# BOTTOM_BRD_v_1_0_2.net
KiCad netlist of a schematic drawn in EAGLE
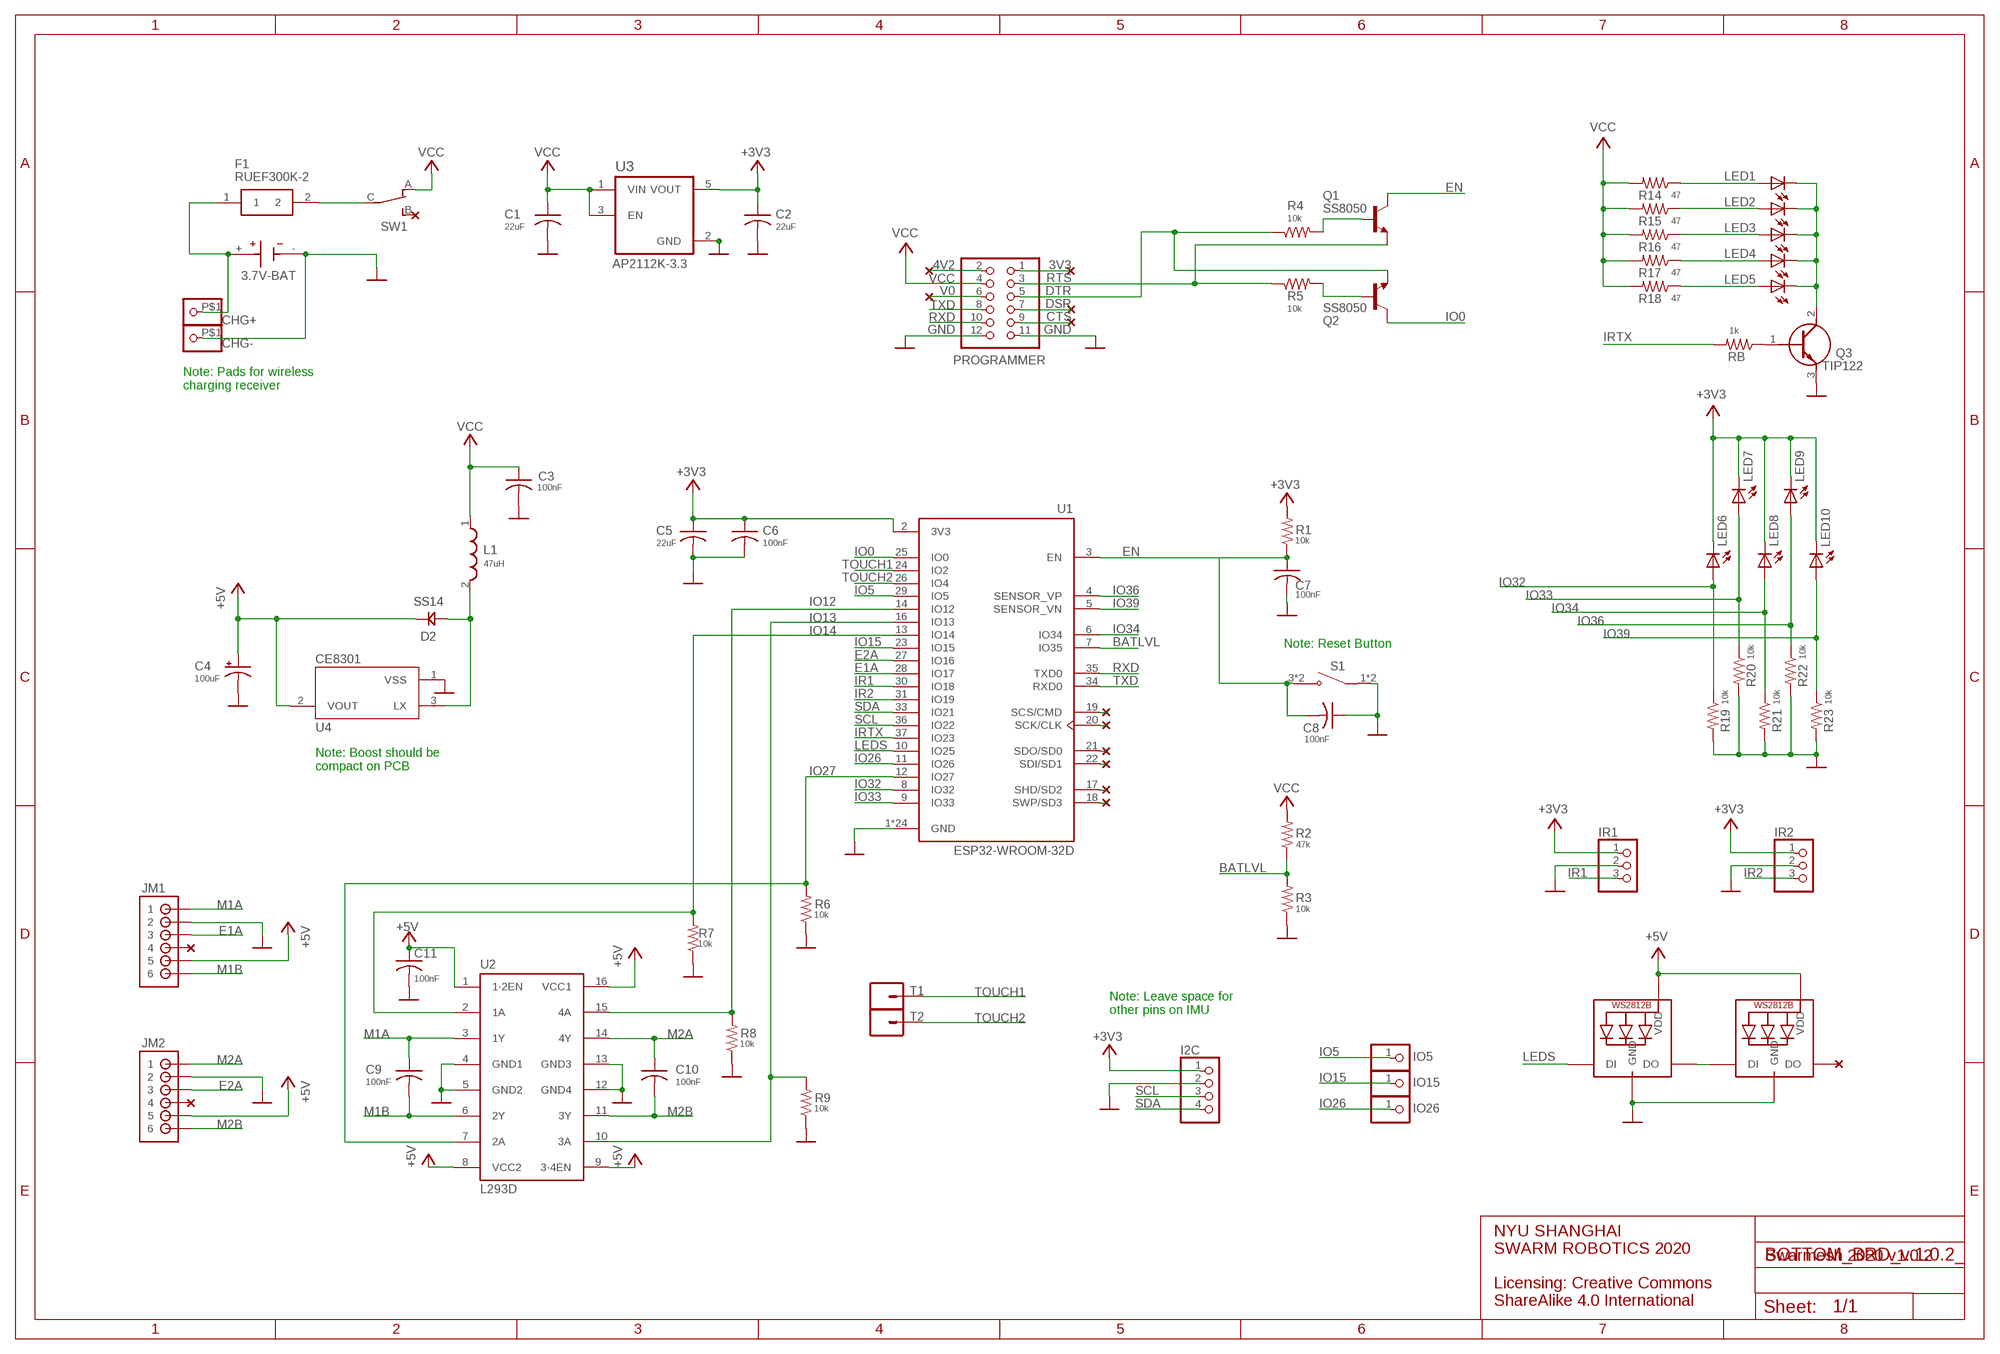
[diagram p0: schematic, sheet 1]

(export (version "E")
  (design (tool "Eeschema 10.0.6"))
  (components
    (comp (ref "BT1")
      (value "3.7V-BAT")
      (footprint "eagle-import:BAT_6S-AA")
      (fields (field (name "MF") "MPD") (field (name "MP") "6S-AA"))
      (libsource (lib "eagle-import") (part "6S-AA"))
    )
    (comp (ref "C1")
      (value "22uF")
      (footprint "eagle-import:C0805")
      (libsource (lib "eagle-import") (part "C-USC0805"))
    )
    (comp (ref "C2")
      (value "22uF")
      (footprint "eagle-import:C0805")
      (libsource (lib "eagle-import") (part "C-USC0805"))
    )
    (comp (ref "C3")
      (value "100nF")
      (footprint "eagle-import:C0805")
      (libsource (lib "eagle-import") (part "C-USC0805"))
    )
    (comp (ref "C4")
      (value "100uF")
      (footprint "eagle-import:153CLV-0605")
      (libsource (lib "eagle-import") (part "CPOL-US153CLV-0605"))
    )
    (comp (ref "C5")
      (value "22uF")
      (footprint "eagle-import:C0805")
      (libsource (lib "eagle-import") (part "C-USC0805"))
    )
    (comp (ref "C6")
      (value "100nF")
      (footprint "eagle-import:C0805")
      (libsource (lib "eagle-import") (part "C-USC0805"))
    )
    (comp (ref "C7")
      (value "100nF")
      (footprint "eagle-import:C0805")
      (libsource (lib "eagle-import") (part "C-USC0805"))
    )
    (comp (ref "C8")
      (value "100nF")
      (footprint "eagle-import:C0805")
      (libsource (lib "eagle-import") (part "C-USC0805"))
    )
    (comp (ref "C9")
      (value "100nF")
      (footprint "eagle-import:C0805")
      (libsource (lib "eagle-import") (part "C-USC0805"))
    )
    (comp (ref "C10")
      (value "100nF")
      (footprint "eagle-import:C0805")
      (libsource (lib "eagle-import") (part "C-USC0805"))
    )
    (comp (ref "C11")
      (value "100nF")
      (footprint "eagle-import:C0805")
      (libsource (lib "eagle-import") (part "C-USC0805"))
    )
    (comp (ref "CHARGING")
      (value "WS2812B5050")
      (footprint "eagle-import:WS2812B")
      (libsource (lib "eagle-import") (part "WS2812B5050"))
    )
    (comp (ref "CHG+")
      (value "PINHD-1X1-BIGPOGO")
      (footprint "eagle-import:1X1-BIGPOGO")
      (libsource (lib "eagle-import") (part "PINHD-1X1-BIGPOGO"))
    )
    (comp (ref "CHG-")
      (value "PINHD-1X1-BIGPOGO")
      (footprint "eagle-import:1X1-BIGPOGO")
      (libsource (lib "eagle-import") (part "PINHD-1X1-BIGPOGO"))
    )
    (comp (ref "D2")
      (value "SS14")
      (footprint "eagle-import:DO214")
      (fields (field (name "MF") "ON Semiconductor"))
      (libsource (lib "eagle-import") (part "SS14"))
    )
    (comp (ref "F1")
      (value "RUEF300K-2")
      (footprint "eagle-import:RUEF300K2")
      (libsource (lib "eagle-import") (part "RUEF300K-2"))
    )
    (comp (ref "I2C")
      (value "PINHD-1X4")
      (footprint "eagle-import:1X04")
      (libsource (lib "eagle-import") (part "PINHD-1X4"))
    )
    (comp (ref "IO5")
      (value "PINHD-1X1")
      (footprint "eagle-import:1X01")
      (libsource (lib "eagle-import") (part "pinhead_325_PINHD-1X1"))
    )
    (comp (ref "IO15")
      (value "PINHD-1X1")
      (footprint "eagle-import:1X01")
      (libsource (lib "eagle-import") (part "pinhead_325_PINHD-1X1"))
    )
    (comp (ref "IO26")
      (value "PINHD-1X1")
      (footprint "eagle-import:1X01")
      (libsource (lib "eagle-import") (part "pinhead_325_PINHD-1X1"))
    )
    (comp (ref "IR1")
      (value "PINHD-1X3")
      (footprint "eagle-import:1X03")
      (libsource (lib "eagle-import") (part "PINHD-1X3"))
    )
    (comp (ref "IR2")
      (value "PINHD-1X3")
      (footprint "eagle-import:1X03")
      (libsource (lib "eagle-import") (part "PINHD-1X3"))
    )
    (comp (ref "JM1")
      (value "B6B-ZR")
      (footprint "eagle-import:B6B-ZR")
      (fields (field (name "MF") "JST"))
      (libsource (lib "eagle-import") (part "B6B-ZR"))
    )
    (comp (ref "JM2")
      (value "B6B-ZR")
      (footprint "eagle-import:B6B-ZR")
      (fields (field (name "MF") "JST"))
      (libsource (lib "eagle-import") (part "B6B-ZR"))
    )
    (comp (ref "L1")
      (value "47uH")
      (footprint "eagle-import:INDP5858X480N")
      (fields (field (name "MF") "Bourns") (field (name "MP") "SDR0604-100KL"))
      (libsource (lib "eagle-import") (part "SDR0604-100KL"))
    )
    (comp (ref "LED1")
      (value "LED5MM")
      (footprint "eagle-import:LED5MM")
      (libsource (lib "eagle-import") (part "LED5MM"))
    )
    (comp (ref "LED2")
      (value "LED5MM")
      (footprint "eagle-import:LED5MM")
      (libsource (lib "eagle-import") (part "LED5MM"))
    )
    (comp (ref "LED3")
      (value "LED5MM")
      (footprint "eagle-import:LED5MM")
      (libsource (lib "eagle-import") (part "LED5MM"))
    )
    (comp (ref "LED4")
      (value "LED5MM")
      (footprint "eagle-import:LED5MM")
      (libsource (lib "eagle-import") (part "LED5MM"))
    )
    (comp (ref "LED5")
      (value "LED5MM")
      (footprint "eagle-import:LED5MM")
      (libsource (lib "eagle-import") (part "LED5MM"))
    )
    (comp (ref "LED6")
      (value "LED5MM")
      (footprint "eagle-import:LED5MM")
      (libsource (lib "eagle-import") (part "LED5MM"))
    )
    (comp (ref "LED7")
      (value "LED5MM")
      (footprint "eagle-import:LED5MM")
      (libsource (lib "eagle-import") (part "LED5MM"))
    )
    (comp (ref "LED8")
      (value "LED5MM")
      (footprint "eagle-import:LED5MM")
      (libsource (lib "eagle-import") (part "LED5MM"))
    )
    (comp (ref "LED9")
      (value "LED5MM")
      (footprint "eagle-import:LED5MM")
      (libsource (lib "eagle-import") (part "LED5MM"))
    )
    (comp (ref "LED10")
      (value "LED5MM")
      (footprint "eagle-import:LED5MM")
      (libsource (lib "eagle-import") (part "LED5MM"))
    )
    (comp (ref "PROGRAMMER")
      (value "PINHD-2X6")
      (footprint "eagle-import:2X06")
      (libsource (lib "eagle-import") (part "PINHD-2X6"))
    )
    (comp (ref "Q1")
      (value "SS8050")
      (footprint "eagle-import:SOT23")
      (libsource (lib "eagle-import") (part "BC850"))
    )
    (comp (ref "Q2")
      (value "SS8050")
      (footprint "eagle-import:SOT23")
      (libsource (lib "eagle-import") (part "BC850"))
    )
    (comp (ref "Q3")
      (value "TIP122")
      (footprint "eagle-import:TO270P460X1020X2008-3P")
      (fields (field (name "MOUSER_PART_NUMBER") "511-TIP122"))
      (libsource (lib "eagle-import") (part "TIP122"))
    )
    (comp (ref "R1")
      (value "10k")
      (footprint "eagle-import:M0805")
      (libsource (lib "eagle-import") (part "R-US_M0805"))
    )
    (comp (ref "R2")
      (value "47k")
      (footprint "eagle-import:M0805")
      (libsource (lib "eagle-import") (part "R-US_M0805"))
    )
    (comp (ref "R3")
      (value "10k")
      (footprint "eagle-import:M0805")
      (libsource (lib "eagle-import") (part "R-US_M0805"))
    )
    (comp (ref "R4")
      (value "10k")
      (footprint "eagle-import:M0805")
      (libsource (lib "eagle-import") (part "R-US_M0805"))
    )
    (comp (ref "R5")
      (value "10k")
      (footprint "eagle-import:M0805")
      (libsource (lib "eagle-import") (part "R-US_M0805"))
    )
    (comp (ref "R6")
      (value "10k")
      (footprint "eagle-import:M0805")
      (libsource (lib "eagle-import") (part "R-US_M0805"))
    )
    (comp (ref "R7")
      (value "10k")
      (footprint "eagle-import:M0805")
      (libsource (lib "eagle-import") (part "R-US_M0805"))
    )
    (comp (ref "R8")
      (value "10k")
      (footprint "eagle-import:M0805")
      (libsource (lib "eagle-import") (part "R-US_M0805"))
    )
    (comp (ref "R9")
      (value "10k")
      (footprint "eagle-import:M0805")
      (libsource (lib "eagle-import") (part "R-US_M0805"))
    )
    (comp (ref "R14")
      (value "47")
      (footprint "eagle-import:M0805")
      (libsource (lib "eagle-import") (part "R-US_M0805"))
    )
    (comp (ref "R15")
      (value "47")
      (footprint "eagle-import:M0805")
      (libsource (lib "eagle-import") (part "R-US_M0805"))
    )
    (comp (ref "R16")
      (value "47")
      (footprint "eagle-import:M0805")
      (libsource (lib "eagle-import") (part "R-US_M0805"))
    )
    (comp (ref "R17")
      (value "47")
      (footprint "eagle-import:M0805")
      (libsource (lib "eagle-import") (part "R-US_M0805"))
    )
    (comp (ref "R18")
      (value "47")
      (footprint "eagle-import:M0805")
      (libsource (lib "eagle-import") (part "R-US_M0805"))
    )
    (comp (ref "R19")
      (value "10k")
      (footprint "eagle-import:M0805")
      (libsource (lib "eagle-import") (part "R-US_M0805"))
    )
    (comp (ref "R20")
      (value "10k")
      (footprint "eagle-import:M0805")
      (libsource (lib "eagle-import") (part "R-US_M0805"))
    )
    (comp (ref "R21")
      (value "10k")
      (footprint "eagle-import:M0805")
      (libsource (lib "eagle-import") (part "R-US_M0805"))
    )
    (comp (ref "R22")
      (value "10k")
      (footprint "eagle-import:M0805")
      (libsource (lib "eagle-import") (part "R-US_M0805"))
    )
    (comp (ref "R23")
      (value "10k")
      (footprint "eagle-import:M0805")
      (libsource (lib "eagle-import") (part "R-US_M0805"))
    )
    (comp (ref "RB")
      (value "1k")
      (footprint "eagle-import:M0805")
      (libsource (lib "eagle-import") (part "R-US_M0805"))
    )
    (comp (ref "S1")
      (value "2-1437565-9")
      (footprint "eagle-import:SW_2-1437565-9")
      (fields (field (name "MF") "TE Connectivity"))
      (libsource (lib "eagle-import") (part "2-1437565-9"))
    )
    (comp (ref "STATE")
      (value "WS2812B5050")
      (footprint "eagle-import:WS2812B")
      (libsource (lib "eagle-import") (part "WS2812B5050"))
    )
    (comp (ref "SW1")
      (value "CS12ANW03")
      (footprint "eagle-import:CS12ANW03")
      (fields (field (name "MF") "NKK Switches"))
      (libsource (lib "eagle-import") (part "CS12ANW03"))
    )
    (comp (ref "T1")
      (value "CONN_01SPRING-CONN")
      (footprint "eagle-import:SPRING-CONNECTOR")
      (libsource (lib "eagle-import") (part "CONN_01SPRING-CONN"))
    )
    (comp (ref "T2")
      (value "CONN_01SPRING-CONN")
      (footprint "eagle-import:SPRING-CONNECTOR")
      (libsource (lib "eagle-import") (part "CONN_01SPRING-CONN"))
    )
    (comp (ref "U1")
      (value "ESP32-WROOM-32D")
      (footprint "eagle-import:MODULE_ESP32-WROOM-32D")
      (fields (field (name "MF") "Espressif Systems"))
      (libsource (lib "eagle-import") (part "ESP32-WROOM-32D"))
    )
    (comp (ref "U2")
      (value "L293D")
      (footprint "eagle-import:DIL16")
      (libsource (lib "eagle-import") (part "L293D"))
    )
    (comp (ref "U3")
      (value "AP2112K-3.3")
      (footprint "eagle-import:SOT95P285X140-5N")
      (fields (field (name "MF") "Diodes Inc.") (field (name "MP") "AP2112K-3.3TRG1"))
      (libsource (lib "eagle-import") (part "AP2112K-3.3TRG1"))
    )
    (comp (ref "U4")
      (value "CE8301")
      (footprint "eagle-import:REG_MCP1702T-3302E_MB")
      (fields (field (name "MF") "Microchip") (field (name "MP") "MCP1702T-3302E/MB"))
      (libsource (lib "eagle-import") (part "MCP1702T-3302E/MB"))
    )
  )
  (nets
    (net (code "1") (name "+3V3") (class "Default")
      (node (ref "C2") (pin "1") (pinfunction "1_1") (pintype "passive"))
      (node (ref "C5") (pin "1") (pinfunction "1_1") (pintype "passive"))
      (node (ref "C6") (pin "1") (pinfunction "1_1") (pintype "passive"))
      (node (ref "I2C") (pin "1") (pinfunction "1_1") (pintype "passive"))
      (node (ref "IR1") (pin "1") (pinfunction "1_1") (pintype "passive"))
      (node (ref "IR2") (pin "1") (pinfunction "1_1") (pintype "passive"))
      (node (ref "LED10") (pin "K") (pinfunction "C_K") (pintype "passive"))
      (node (ref "LED6") (pin "K") (pinfunction "C_K") (pintype "passive"))
      (node (ref "LED7") (pin "K") (pinfunction "C_K") (pintype "passive"))
      (node (ref "LED8") (pin "K") (pinfunction "C_K") (pintype "passive"))
      (node (ref "LED9") (pin "K") (pinfunction "C_K") (pintype "passive"))
      (node (ref "R1") (pin "2") (pinfunction "2_2") (pintype "passive"))
      (node (ref "U1") (pin "2") (pinfunction "3V3_2") (pintype "power_in"))
      (node (ref "U3") (pin "5") (pinfunction "VOUT_5") (pintype "power_in"))
    )
    (net (code "2") (name "+5V") (class "Default")
      (node (ref "C11") (pin "1") (pinfunction "1_1") (pintype "passive"))
      (node (ref "C4") (pin "+") (pinfunction "+_+") (pintype "passive"))
      (node (ref "CHARGING") (pin "1-VDD") (pinfunction "VDD_1-VDD") (pintype "power_in"))
      (node (ref "D2") (pin "CATHODE") (pinfunction "KATHODE_CATHODE") (pintype "bidirectional"))
      (node (ref "JM1") (pin "5") (pinfunction "5_5") (pintype "bidirectional"))
      (node (ref "JM2") (pin "5") (pinfunction "5_5") (pintype "bidirectional"))
      (node (ref "STATE") (pin "1-VDD") (pinfunction "VDD_1-VDD") (pintype "power_in"))
      (node (ref "U2") (pin "1") (pinfunction "1-2EN_1") (pintype "input"))
      (node (ref "U2") (pin "16") (pinfunction "VCC1_16") (pintype "power_in"))
      (node (ref "U2") (pin "8") (pinfunction "VCC2_8") (pintype "power_in"))
      (node (ref "U2") (pin "9") (pinfunction "3-4EN_9") (pintype "input"))
      (node (ref "U4") (pin "2") (pinfunction "VOUT_2") (pintype "input"))
    )
    (net (code "3") (name "/3V3") (class "Default")
      (node (ref "PROGRAMMER") (pin "1") (pinfunction "1_1") (pintype "passive"))
    )
    (net (code "4") (name "/4V2") (class "Default")
      (node (ref "PROGRAMMER") (pin "2") (pinfunction "2_2") (pintype "passive"))
    )
    (net (code "5") (name "/BATLVL") (class "Default")
      (node (ref "R2") (pin "1") (pinfunction "1_1") (pintype "passive"))
      (node (ref "R3") (pin "2") (pinfunction "2_2") (pintype "passive"))
      (node (ref "U1") (pin "7") (pinfunction "IO35_7") (pintype "input"))
    )
    (net (code "6") (name "/CTS") (class "Default")
      (node (ref "PROGRAMMER") (pin "9") (pinfunction "9_9") (pintype "passive"))
    )
    (net (code "7") (name "/DSR") (class "Default")
      (node (ref "PROGRAMMER") (pin "7") (pinfunction "7_7") (pintype "passive"))
    )
    (net (code "8") (name "/DTR") (class "Default")
      (node (ref "PROGRAMMER") (pin "5") (pinfunction "5_5") (pintype "passive"))
      (node (ref "Q2") (pin "2") (pinfunction "E_2") (pintype "passive"))
      (node (ref "R4") (pin "1") (pinfunction "1_1") (pintype "passive"))
    )
    (net (code "9") (name "/E1A") (class "Default")
      (node (ref "JM1") (pin "3") (pinfunction "3_3") (pintype "bidirectional"))
      (node (ref "U1") (pin "28") (pinfunction "IO17_28") (pintype "bidirectional"))
    )
    (net (code "10") (name "/E2A") (class "Default")
      (node (ref "JM2") (pin "3") (pinfunction "3_3") (pintype "bidirectional"))
      (node (ref "U1") (pin "27") (pinfunction "IO16_27") (pintype "bidirectional"))
    )
    (net (code "11") (name "/EN") (class "Default")
      (node (ref "C7") (pin "1") (pinfunction "1_1") (pintype "passive"))
      (node (ref "C8") (pin "2") (pinfunction "2_2") (pintype "passive"))
      (node (ref "Q1") (pin "3") (pinfunction "C_3") (pintype "passive"))
      (node (ref "R1") (pin "1") (pinfunction "1_1") (pintype "passive"))
      (node (ref "S1") (pin "3") (pinfunction "NO_3") (pintype "passive"))
      (node (ref "S1") (pin "4") (pinfunction "NO_4") (pintype "passive"))
      (node (ref "U1") (pin "3") (pinfunction "EN_3") (pintype "input"))
    )
    (net (code "12") (name "/IO0") (class "Default")
      (node (ref "Q2") (pin "3") (pinfunction "C_3") (pintype "passive"))
      (node (ref "U1") (pin "25") (pinfunction "IO0_25") (pintype "bidirectional"))
    )
    (net (code "13") (name "/IO5") (class "Default")
      (node (ref "IO5") (pin "1") (pinfunction "1_1") (pintype "passive"))
      (node (ref "U1") (pin "29") (pinfunction "IO5_29") (pintype "bidirectional"))
    )
    (net (code "14") (name "/IO12") (class "Default")
      (node (ref "R8") (pin "2") (pinfunction "2_2") (pintype "passive"))
      (node (ref "U1") (pin "14") (pinfunction "IO12_14") (pintype "bidirectional"))
      (node (ref "U2") (pin "15") (pinfunction "4A_15") (pintype "input"))
    )
    (net (code "15") (name "/IO13") (class "Default")
      (node (ref "R9") (pin "2") (pinfunction "2_2") (pintype "passive"))
      (node (ref "U1") (pin "16") (pinfunction "IO13_16") (pintype "bidirectional"))
      (node (ref "U2") (pin "10") (pinfunction "3A_10") (pintype "input"))
    )
    (net (code "16") (name "/IO14") (class "Default")
      (node (ref "R7") (pin "2") (pinfunction "2_2") (pintype "passive"))
      (node (ref "U1") (pin "13") (pinfunction "IO14_13") (pintype "bidirectional"))
      (node (ref "U2") (pin "2") (pinfunction "1A_2") (pintype "input"))
    )
    (net (code "17") (name "/IO15") (class "Default")
      (node (ref "IO15") (pin "1") (pinfunction "1_1") (pintype "passive"))
      (node (ref "U1") (pin "23") (pinfunction "IO15_23") (pintype "bidirectional"))
    )
    (net (code "18") (name "/IO26") (class "Default")
      (node (ref "IO26") (pin "1") (pinfunction "1_1") (pintype "passive"))
      (node (ref "U1") (pin "11") (pinfunction "IO26_11") (pintype "bidirectional"))
    )
    (net (code "19") (name "/IO27") (class "Default")
      (node (ref "R6") (pin "2") (pinfunction "2_2") (pintype "passive"))
      (node (ref "U1") (pin "12") (pinfunction "IO27_12") (pintype "bidirectional"))
      (node (ref "U2") (pin "7") (pinfunction "2A_7") (pintype "input"))
    )
    (net (code "20") (name "/IO32") (class "Default")
      (node (ref "LED6") (pin "A") (pinfunction "A_A") (pintype "passive"))
      (node (ref "R19") (pin "1") (pinfunction "1_1") (pintype "passive"))
      (node (ref "U1") (pin "8") (pinfunction "IO32_8") (pintype "bidirectional"))
    )
    (net (code "21") (name "/IO33") (class "Default")
      (node (ref "LED7") (pin "A") (pinfunction "A_A") (pintype "passive"))
      (node (ref "R20") (pin "1") (pinfunction "1_1") (pintype "passive"))
      (node (ref "U1") (pin "9") (pinfunction "IO33_9") (pintype "bidirectional"))
    )
    (net (code "22") (name "/IO34") (class "Default")
      (node (ref "LED8") (pin "A") (pinfunction "A_A") (pintype "passive"))
      (node (ref "R21") (pin "1") (pinfunction "1_1") (pintype "passive"))
      (node (ref "U1") (pin "6") (pinfunction "IO34_6") (pintype "input"))
    )
    (net (code "23") (name "/IO36") (class "Default")
      (node (ref "LED9") (pin "A") (pinfunction "A_A") (pintype "passive"))
      (node (ref "R22") (pin "1") (pinfunction "1_1") (pintype "passive"))
      (node (ref "U1") (pin "4") (pinfunction "SENSOR_VP_4") (pintype "input"))
    )
    (net (code "24") (name "/IO39") (class "Default")
      (node (ref "LED10") (pin "A") (pinfunction "A_A") (pintype "passive"))
      (node (ref "R23") (pin "1") (pinfunction "1_1") (pintype "passive"))
      (node (ref "U1") (pin "5") (pinfunction "SENSOR_VN_5") (pintype "input"))
    )
    (net (code "25") (name "/IR1") (class "Default")
      (node (ref "IR1") (pin "3") (pinfunction "3_3") (pintype "passive"))
      (node (ref "U1") (pin "30") (pinfunction "IO18_30") (pintype "bidirectional"))
    )
    (net (code "26") (name "/IR2") (class "Default")
      (node (ref "IR2") (pin "3") (pinfunction "3_3") (pintype "passive"))
      (node (ref "U1") (pin "31") (pinfunction "IO19_31") (pintype "bidirectional"))
    )
    (net (code "27") (name "/IRTX") (class "Default")
      (node (ref "RB") (pin "2") (pinfunction "2_2") (pintype "passive"))
      (node (ref "U1") (pin "37") (pinfunction "IO23_37") (pintype "bidirectional"))
    )
    (net (code "28") (name "/LEDS") (class "Default")
      (node (ref "CHARGING") (pin "4-DIN") (pinfunction "DI_4-DIN") (pintype "input"))
      (node (ref "U1") (pin "10") (pinfunction "IO25_10") (pintype "bidirectional"))
    )
    (net (code "29") (name "/M1A") (class "Default")
      (node (ref "C9") (pin "1") (pinfunction "1_1") (pintype "passive"))
      (node (ref "JM1") (pin "1") (pinfunction "1_1") (pintype "bidirectional"))
      (node (ref "U2") (pin "3") (pinfunction "1Y_3") (pintype "output"))
    )
    (net (code "30") (name "/M1B") (class "Default")
      (node (ref "C9") (pin "2") (pinfunction "2_2") (pintype "passive"))
      (node (ref "JM1") (pin "6") (pinfunction "6_6") (pintype "bidirectional"))
      (node (ref "U2") (pin "6") (pinfunction "2Y_6") (pintype "output"))
    )
    (net (code "31") (name "/M2A") (class "Default")
      (node (ref "C10") (pin "1") (pinfunction "1_1") (pintype "passive"))
      (node (ref "JM2") (pin "1") (pinfunction "1_1") (pintype "bidirectional"))
      (node (ref "U2") (pin "14") (pinfunction "4Y_14") (pintype "output"))
    )
    (net (code "32") (name "/M2B") (class "Default")
      (node (ref "C10") (pin "2") (pinfunction "2_2") (pintype "passive"))
      (node (ref "JM2") (pin "6") (pinfunction "6_6") (pintype "bidirectional"))
      (node (ref "U2") (pin "11") (pinfunction "3Y_11") (pintype "output"))
    )
    (net (code "33") (name "/RTS") (class "Default")
      (node (ref "PROGRAMMER") (pin "3") (pinfunction "3_3") (pintype "passive"))
      (node (ref "Q1") (pin "2") (pinfunction "E_2") (pintype "passive"))
      (node (ref "R5") (pin "1") (pinfunction "1_1") (pintype "passive"))
    )
    (net (code "34") (name "/RXD") (class "Default")
      (node (ref "PROGRAMMER") (pin "10") (pinfunction "10_10") (pintype "passive"))
      (node (ref "U1") (pin "35") (pinfunction "TXD0_35") (pintype "bidirectional"))
    )
    (net (code "35") (name "/SCL") (class "Default")
      (node (ref "I2C") (pin "3") (pinfunction "3_3") (pintype "passive"))
      (node (ref "U1") (pin "36") (pinfunction "IO22_36") (pintype "bidirectional"))
    )
    (net (code "36") (name "/SDA") (class "Default")
      (node (ref "I2C") (pin "4") (pinfunction "4_4") (pintype "passive"))
      (node (ref "U1") (pin "33") (pinfunction "IO21_33") (pintype "bidirectional"))
    )
    (net (code "37") (name "/TOUCH1") (class "Default")
      (node (ref "T1") (pin "P$2") (pinfunction "1_P$2") (pintype "passive"))
      (node (ref "U1") (pin "24") (pinfunction "IO2_24") (pintype "bidirectional"))
    )
    (net (code "38") (name "/TOUCH2") (class "Default")
      (node (ref "T2") (pin "P$2") (pinfunction "1_P$2") (pintype "passive"))
      (node (ref "U1") (pin "26") (pinfunction "IO4_26") (pintype "bidirectional"))
    )
    (net (code "39") (name "/TXD") (class "Default")
      (node (ref "PROGRAMMER") (pin "8") (pinfunction "8_8") (pintype "passive"))
      (node (ref "U1") (pin "34") (pinfunction "RXD0_34") (pintype "bidirectional"))
    )
    (net (code "40") (name "/V0") (class "Default")
      (node (ref "PROGRAMMER") (pin "6") (pinfunction "6_6") (pintype "passive"))
    )
    (net (code "41") (name "GND") (class "Default")
      (node (ref "BT1") (pin "-") (pinfunction "-_-") (pintype "passive"))
      (node (ref "C1") (pin "2") (pinfunction "2_2") (pintype "passive"))
      (node (ref "C11") (pin "2") (pinfunction "2_2") (pintype "passive"))
      (node (ref "C2") (pin "2") (pinfunction "2_2") (pintype "passive"))
      (node (ref "C3") (pin "2") (pinfunction "2_2") (pintype "passive"))
      (node (ref "C4") (pin "-") (pinfunction "-_-") (pintype "passive"))
      (node (ref "C5") (pin "2") (pinfunction "2_2") (pintype "passive"))
      (node (ref "C6") (pin "2") (pinfunction "2_2") (pintype "passive"))
      (node (ref "C7") (pin "2") (pinfunction "2_2") (pintype "passive"))
      (node (ref "C8") (pin "1") (pinfunction "1_1") (pintype "passive"))
      (node (ref "CHARGING") (pin "3-GND") (pinfunction "GND_3-GND") (pintype "power_in"))
      (node (ref "CHG-") (pin "P$1") (pinfunction "1_P$1") (pintype "passive"))
      (node (ref "I2C") (pin "2") (pinfunction "2_2") (pintype "passive"))
      (node (ref "IR1") (pin "2") (pinfunction "2_2") (pintype "passive"))
      (node (ref "IR2") (pin "2") (pinfunction "2_2") (pintype "passive"))
      (node (ref "JM1") (pin "2") (pinfunction "2_2") (pintype "bidirectional"))
      (node (ref "JM2") (pin "2") (pinfunction "2_2") (pintype "bidirectional"))
      (node (ref "PROGRAMMER") (pin "11") (pinfunction "11_11") (pintype "passive"))
      (node (ref "PROGRAMMER") (pin "12") (pinfunction "12_12") (pintype "passive"))
      (node (ref "Q3") (pin "3") (pinfunction "E_3") (pintype "bidirectional"))
      (node (ref "R19") (pin "2") (pinfunction "2_2") (pintype "passive"))
      (node (ref "R20") (pin "2") (pinfunction "2_2") (pintype "passive"))
      (node (ref "R21") (pin "2") (pinfunction "2_2") (pintype "passive"))
      (node (ref "R22") (pin "2") (pinfunction "2_2") (pintype "passive"))
      (node (ref "R23") (pin "2") (pinfunction "2_2") (pintype "passive"))
      (node (ref "R3") (pin "1") (pinfunction "1_1") (pintype "passive"))
      (node (ref "R6") (pin "1") (pinfunction "1_1") (pintype "passive"))
      (node (ref "R7") (pin "1") (pinfunction "1_1") (pintype "passive"))
      (node (ref "R8") (pin "1") (pinfunction "1_1") (pintype "passive"))
      (node (ref "R9") (pin "1") (pinfunction "1_1") (pintype "passive"))
      (node (ref "S1") (pin "1") (pinfunction "COM_1") (pintype "passive"))
      (node (ref "S1") (pin "2") (pinfunction "COM_2") (pintype "passive"))
      (node (ref "STATE") (pin "3-GND") (pinfunction "GND_3-GND") (pintype "power_in"))
      (node (ref "U1") (pin "1") (pinfunction "GND_1") (pintype "power_in"))
      (node (ref "U1") (pin "15") (pinfunction "GND_15") (pintype "power_in"))
      (node (ref "U1") (pin "38") (pinfunction "GND_38") (pintype "power_in"))
      (node (ref "U1") (pin "39_1") (pinfunction "GND_39_1") (pintype "power_in"))
      (node (ref "U1") (pin "39_10") (pinfunction "GND_39_10") (pintype "power_in"))
      (node (ref "U1") (pin "39_11") (pinfunction "GND_39_11") (pintype "power_in"))
      (node (ref "U1") (pin "39_12") (pinfunction "GND_39_12") (pintype "power_in"))
      (node (ref "U1") (pin "39_13") (pinfunction "GND_39_13") (pintype "power_in"))
      (node (ref "U1") (pin "39_14") (pinfunction "GND_39_14") (pintype "power_in"))
      (node (ref "U1") (pin "39_15") (pinfunction "GND_39_15") (pintype "power_in"))
      (node (ref "U1") (pin "39_16") (pinfunction "GND_39_16") (pintype "power_in"))
      (node (ref "U1") (pin "39_17") (pinfunction "GND_39_17") (pintype "power_in"))
      (node (ref "U1") (pin "39_18") (pinfunction "GND_39_18") (pintype "power_in"))
      (node (ref "U1") (pin "39_19") (pinfunction "GND_39_19") (pintype "power_in"))
      (node (ref "U1") (pin "39_2") (pinfunction "GND_39_2") (pintype "power_in"))
      (node (ref "U1") (pin "39_20") (pinfunction "GND_39_20") (pintype "power_in"))
      (node (ref "U1") (pin "39_21") (pinfunction "GND_39_21") (pintype "power_in"))
      (node (ref "U1") (pin "39_3") (pinfunction "GND_39_3") (pintype "power_in"))
      (node (ref "U1") (pin "39_4") (pinfunction "GND_39_4") (pintype "power_in"))
      (node (ref "U1") (pin "39_5") (pinfunction "GND_39_5") (pintype "power_in"))
      (node (ref "U1") (pin "39_6") (pinfunction "GND_39_6") (pintype "power_in"))
      (node (ref "U1") (pin "39_7") (pinfunction "GND_39_7") (pintype "power_in"))
      (node (ref "U1") (pin "39_8") (pinfunction "GND_39_8") (pintype "power_in"))
      (node (ref "U1") (pin "39_9") (pinfunction "GND_39_9") (pintype "power_in"))
      (node (ref "U2") (pin "12") (pinfunction "GND4_12") (pintype "power_in"))
      (node (ref "U2") (pin "13") (pinfunction "GND3_13") (pintype "power_in"))
      (node (ref "U2") (pin "4") (pinfunction "GND1_4") (pintype "power_in"))
      (node (ref "U2") (pin "5") (pinfunction "GND2_5") (pintype "power_in"))
      (node (ref "U3") (pin "2") (pinfunction "GND_2") (pintype "power_in"))
      (node (ref "U4") (pin "1") (pinfunction "VSS_1") (pintype "power_in"))
    )
    (net (code "42") (name "Net-(CHARGING-DO)") (class "Default")
      (node (ref "CHARGING") (pin "2-DOUT") (pinfunction "DO_2-DOUT") (pintype "output"))
      (node (ref "STATE") (pin "4-DIN") (pinfunction "DI_4-DIN") (pintype "input"))
    )
    (net (code "43") (name "Net-(CHG+-1)") (class "Default")
      (node (ref "BT1") (pin "+") (pinfunction "+_+") (pintype "passive"))
      (node (ref "CHG+") (pin "P$1") (pinfunction "1_P$1") (pintype "passive"))
      (node (ref "F1") (pin "1") (pinfunction "1_1") (pintype "bidirectional"))
    )
    (net (code "44") (name "Net-(F1-Pad2)") (class "Default")
      (node (ref "F1") (pin "2") (pinfunction "2_2") (pintype "bidirectional"))
      (node (ref "SW1") (pin "C") (pinfunction "C_C") (pintype "passive"))
    )
    (net (code "45") (name "Net-(LED1-C)") (class "Default")
      (node (ref "LED1") (pin "K") (pinfunction "C_K") (pintype "passive"))
      (node (ref "LED2") (pin "K") (pinfunction "C_K") (pintype "passive"))
      (node (ref "LED3") (pin "K") (pinfunction "C_K") (pintype "passive"))
      (node (ref "LED4") (pin "K") (pinfunction "C_K") (pintype "passive"))
      (node (ref "LED5") (pin "K") (pinfunction "C_K") (pintype "passive"))
      (node (ref "Q3") (pin "2") (pinfunction "C_2") (pintype "bidirectional"))
    )
    (net (code "46") (name "Net-(LED1-PadA)") (class "Default")
      (node (ref "LED1") (pin "A") (pinfunction "A_A") (pintype "passive"))
      (node (ref "R14") (pin "1") (pinfunction "1_1") (pintype "passive"))
    )
    (net (code "47") (name "Net-(LED2-PadA)") (class "Default")
      (node (ref "LED2") (pin "A") (pinfunction "A_A") (pintype "passive"))
      (node (ref "R15") (pin "1") (pinfunction "1_1") (pintype "passive"))
    )
    (net (code "48") (name "Net-(LED3-PadA)") (class "Default")
      (node (ref "LED3") (pin "A") (pinfunction "A_A") (pintype "passive"))
      (node (ref "R16") (pin "1") (pinfunction "1_1") (pintype "passive"))
    )
    (net (code "49") (name "Net-(LED4-PadA)") (class "Default")
      (node (ref "LED4") (pin "A") (pinfunction "A_A") (pintype "passive"))
      (node (ref "R17") (pin "1") (pinfunction "1_1") (pintype "passive"))
    )
    (net (code "50") (name "Net-(LED5-PadA)") (class "Default")
      (node (ref "LED5") (pin "A") (pinfunction "A_A") (pintype "passive"))
      (node (ref "R18") (pin "1") (pinfunction "1_1") (pintype "passive"))
    )
    (net (code "51") (name "Net-(Q1-B)") (class "Default")
      (node (ref "Q1") (pin "1") (pinfunction "B_1") (pintype "passive"))
      (node (ref "R4") (pin "2") (pinfunction "2_2") (pintype "passive"))
    )
    (net (code "52") (name "Net-(Q2-B)") (class "Default")
      (node (ref "Q2") (pin "1") (pinfunction "B_1") (pintype "passive"))
      (node (ref "R5") (pin "2") (pinfunction "2_2") (pintype "passive"))
    )
    (net (code "53") (name "Net-(Q3-B)") (class "Default")
      (node (ref "Q3") (pin "1") (pinfunction "B_1") (pintype "bidirectional"))
      (node (ref "RB") (pin "1") (pinfunction "1_1") (pintype "passive"))
    )
    (net (code "54") (name "Net-(U4-LX)") (class "Default")
      (node (ref "D2") (pin "ANODE") (pinfunction "ANODE_ANODE") (pintype "bidirectional"))
      (node (ref "L1") (pin "2") (pinfunction "2_2") (pintype "passive"))
      (node (ref "U4") (pin "3") (pinfunction "LX_3") (pintype "output"))
    )
    (net (code "55") (name "VCC") (class "Default")
      (node (ref "C1") (pin "1") (pinfunction "1_1") (pintype "passive"))
      (node (ref "C3") (pin "1") (pinfunction "1_1") (pintype "passive"))
      (node (ref "L1") (pin "1") (pinfunction "1_1") (pintype "passive"))
      (node (ref "PROGRAMMER") (pin "4") (pinfunction "4_4") (pintype "passive"))
      (node (ref "R14") (pin "2") (pinfunction "2_2") (pintype "passive"))
      (node (ref "R15") (pin "2") (pinfunction "2_2") (pintype "passive"))
      (node (ref "R16") (pin "2") (pinfunction "2_2") (pintype "passive"))
      (node (ref "R17") (pin "2") (pinfunction "2_2") (pintype "passive"))
      (node (ref "R18") (pin "2") (pinfunction "2_2") (pintype "passive"))
      (node (ref "R2") (pin "2") (pinfunction "2_2") (pintype "passive"))
      (node (ref "SW1") (pin "A") (pinfunction "A_A") (pintype "passive"))
      (node (ref "U3") (pin "1") (pinfunction "VIN_1") (pintype "power_in"))
      (node (ref "U3") (pin "3") (pinfunction "EN_3") (pintype "input"))
    )
    (net (code "56") (name "unconnected-(JM1-Pad4)") (class "Default")
      (node (ref "JM1") (pin "4") (pinfunction "4_4") (pintype "bidirectional"))
    )
    (net (code "57") (name "unconnected-(JM2-Pad4)") (class "Default")
      (node (ref "JM2") (pin "4") (pinfunction "4_4") (pintype "bidirectional"))
    )
    (net (code "58") (name "unconnected-(STATE-DO-Pad2-DOUT)") (class "Default")
      (node (ref "STATE") (pin "2-DOUT") (pinfunction "DO_2-DOUT") (pintype "output"))
    )
    (net (code "59") (name "unconnected-(SW1-PadB)") (class "Default")
      (node (ref "SW1") (pin "B") (pinfunction "B_B") (pintype "passive"))
    )
    (net (code "60") (name "unconnected-(U1-SCK{slash}CLK-Pad20)") (class "Default")
      (node (ref "U1") (pin "20") (pinfunction "SCK/CLK_20") (pintype "bidirectional"))
    )
    (net (code "61") (name "unconnected-(U1-SCS{slash}CMD-Pad19)") (class "Default")
      (node (ref "U1") (pin "19") (pinfunction "SCS/CMD_19") (pintype "bidirectional"))
    )
    (net (code "62") (name "unconnected-(U1-SDI{slash}SD1-Pad22)") (class "Default")
      (node (ref "U1") (pin "22") (pinfunction "SDI/SD1_22") (pintype "bidirectional"))
    )
    (net (code "63") (name "unconnected-(U1-SDO{slash}SD0-Pad21)") (class "Default")
      (node (ref "U1") (pin "21") (pinfunction "SDO/SD0_21") (pintype "bidirectional"))
    )
    (net (code "64") (name "unconnected-(U1-SHD{slash}SD2-Pad17)") (class "Default")
      (node (ref "U1") (pin "17") (pinfunction "SHD/SD2_17") (pintype "bidirectional"))
    )
    (net (code "65") (name "unconnected-(U1-SWP{slash}SD3-Pad18)") (class "Default")
      (node (ref "U1") (pin "18") (pinfunction "SWP/SD3_18") (pintype "bidirectional"))
    )
  )
)
